# PWM_Sensor.net
KiCad netlist of a schematic drawn in Altium Designer
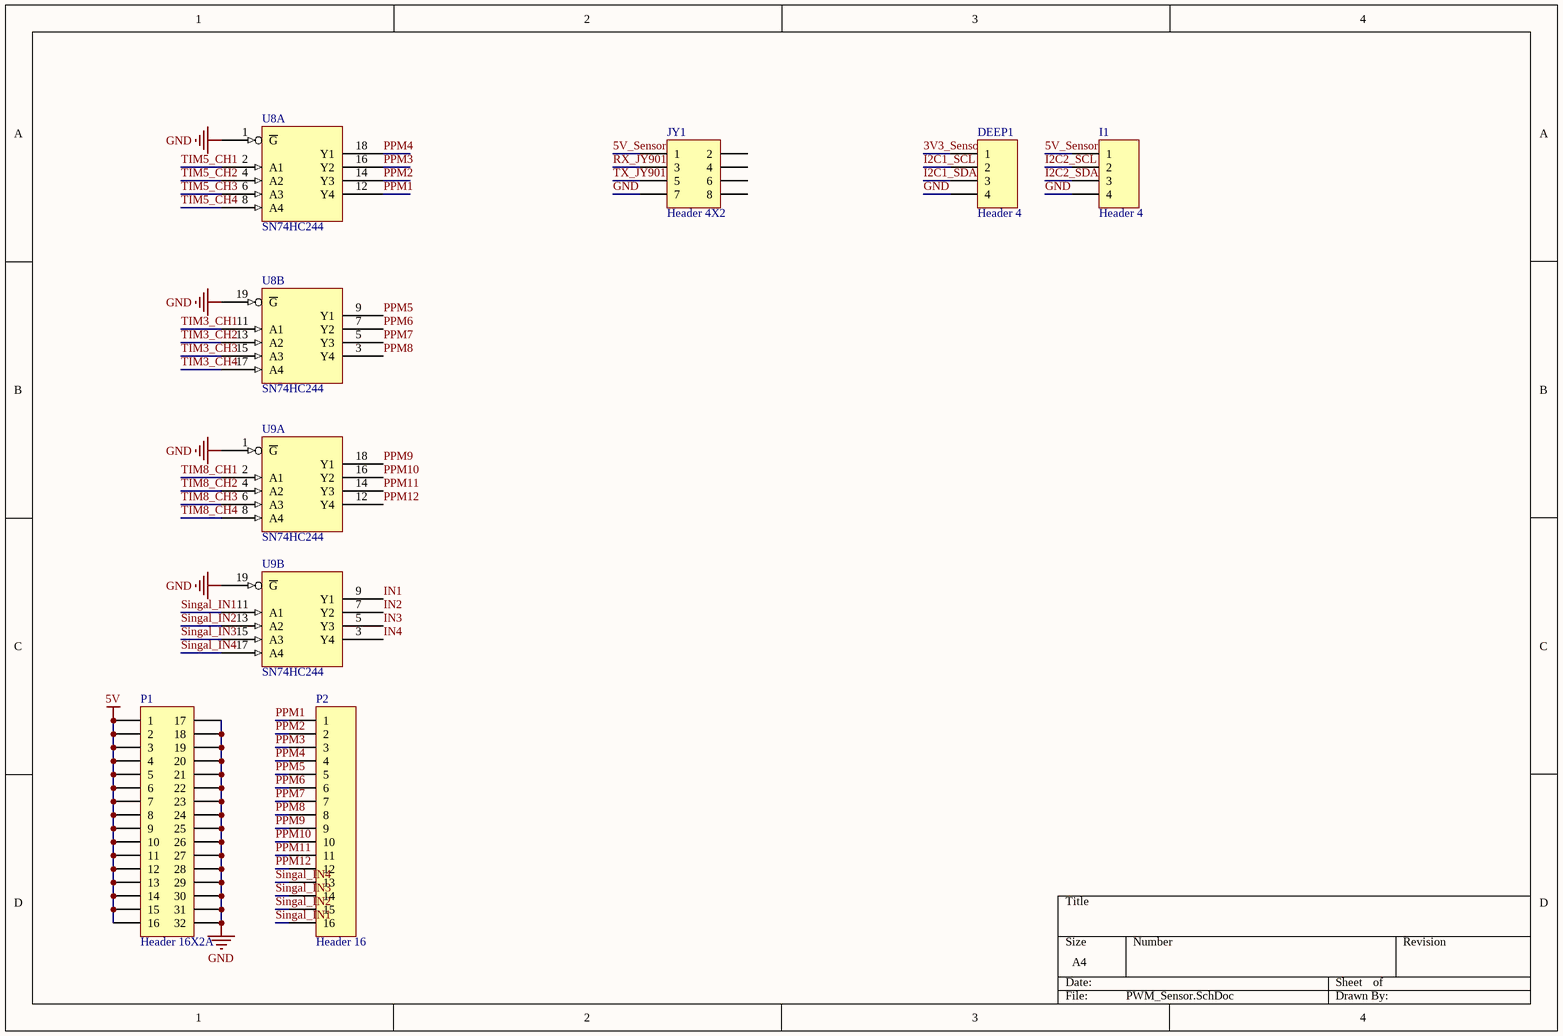
[diagram p0: PWM_Sensor.SchDoc]

(export (version "E")
  (design (tool "Eeschema 10.0.6"))
  (components
    (comp (ref "DEEP1")
      (value "Header 4")
      (footprint "XH2.54_4P")
      (description "Header, 4-Pin")
      (fields (field (name "PUBLISHER") "Altium Limited"))
      (libsource (lib "Miscellaneous Connectors") (part "Header 4"))
    )
    (comp (ref "I1")
      (value "Header 4")
      (footprint "XH2.54_4P")
      (description "Header, 4-Pin")
      (fields (field (name "PUBLISHER") "Altium Limited"))
      (libsource (lib "Miscellaneous Connectors") (part "Header 4"))
    )
    (comp (ref "JY1")
      (value "Header 4X2")
      (footprint "JY901_2")
      (description "Header, 4-Pin, Dual row")
      (fields (field (name "PUBLISHER") "Altium Limited"))
      (libsource (lib "Miscellaneous Connectors") (part "Header 4X2"))
    )
    (comp (ref "P1")
      (value "Header 16X2A")
      (footprint "HDR2X16_CEN")
      (description "Header, 16-Pin, Dual row")
      (fields (field (name "PUBLISHER") "Altium Limited"))
      (libsource (lib "Miscellaneous Connectors") (part "Header 16X2A"))
    )
    (comp (ref "P2")
      (value "Header 16")
      (footprint "HDR1X16")
      (description "Header, 16-Pin")
      (fields (field (name "PUBLISHER") "Altium Limited"))
      (libsource (lib "Miscellaneous Connectors") (part "Header 16"))
    )
    (comp (ref "U8")
      (value "SN74HC244")
      (footprint "SOIC-20_300mil")
      (description "OCTAL BUF AND LIN DRV 3SO")
      (libsource (lib "CMOS&TTL74") (part "SN74HC244"))
    )
    (comp (ref "U9")
      (value "SN74HC244")
      (footprint "SOIC-20_300mil")
      (description "OCTAL BUF AND LIN DRV 3SO")
      (libsource (lib "CMOS&TTL74") (part "SN74HC244"))
    )
  )
  (nets
    (net (code "1") (name "/3V3_Sensor") (class "Default")
      (node (ref "DEEP1") (pin "1") (pinfunction "1_1") (pintype "passive"))
    )
    (net (code "2") (name "/5V_Sensor") (class "Default")
      (node (ref "I1") (pin "1") (pinfunction "1_1") (pintype "passive"))
      (node (ref "JY1") (pin "1") (pinfunction "1_1") (pintype "passive"))
    )
    (net (code "3") (name "/I2C1_SCL") (class "Default")
      (node (ref "DEEP1") (pin "2") (pinfunction "2_2") (pintype "passive"))
    )
    (net (code "4") (name "/I2C1_SDA") (class "Default")
      (node (ref "DEEP1") (pin "3") (pinfunction "3_3") (pintype "passive"))
    )
    (net (code "5") (name "/I2C2_SCL") (class "Default")
      (node (ref "I1") (pin "2") (pinfunction "2_2") (pintype "passive"))
    )
    (net (code "6") (name "/I2C2_SDA") (class "Default")
      (node (ref "I1") (pin "3") (pinfunction "3_3") (pintype "passive"))
    )
    (net (code "7") (name "/IN1") (class "Default")
      (node (ref "U9") (pin "9") (pinfunction "Y1_9") (pintype "tri_state"))
    )
    (net (code "8") (name "/IN2") (class "Default")
      (node (ref "U9") (pin "7") (pinfunction "Y2_7") (pintype "tri_state"))
    )
    (net (code "9") (name "/IN3") (class "Default")
      (node (ref "U9") (pin "5") (pinfunction "Y3_5") (pintype "tri_state"))
    )
    (net (code "10") (name "/IN4") (class "Default")
      (node (ref "U9") (pin "3") (pinfunction "Y4_3") (pintype "tri_state"))
    )
    (net (code "11") (name "/PPM1") (class "Default")
      (node (ref "P2") (pin "1") (pinfunction "1_1") (pintype "passive"))
      (node (ref "U8") (pin "12") (pinfunction "Y4_12") (pintype "tri_state"))
    )
    (net (code "12") (name "/PPM2") (class "Default")
      (node (ref "P2") (pin "2") (pinfunction "2_2") (pintype "passive"))
      (node (ref "U8") (pin "14") (pinfunction "Y3_14") (pintype "tri_state"))
    )
    (net (code "13") (name "/PPM3") (class "Default")
      (node (ref "P2") (pin "3") (pinfunction "3_3") (pintype "passive"))
      (node (ref "U8") (pin "16") (pinfunction "Y2_16") (pintype "tri_state"))
    )
    (net (code "14") (name "/PPM4") (class "Default")
      (node (ref "P2") (pin "4") (pinfunction "4_4") (pintype "passive"))
      (node (ref "U8") (pin "18") (pinfunction "Y1_18") (pintype "tri_state"))
    )
    (net (code "15") (name "/PPM5") (class "Default")
      (node (ref "P2") (pin "5") (pinfunction "5_5") (pintype "passive"))
      (node (ref "U8") (pin "9") (pinfunction "Y1_9") (pintype "tri_state"))
    )
    (net (code "16") (name "/PPM6") (class "Default")
      (node (ref "P2") (pin "6") (pinfunction "6_6") (pintype "passive"))
      (node (ref "U8") (pin "7") (pinfunction "Y2_7") (pintype "tri_state"))
    )
    (net (code "17") (name "/PPM7") (class "Default")
      (node (ref "P2") (pin "7") (pinfunction "7_7") (pintype "passive"))
      (node (ref "U8") (pin "5") (pinfunction "Y3_5") (pintype "tri_state"))
    )
    (net (code "18") (name "/PPM8") (class "Default")
      (node (ref "P2") (pin "8") (pinfunction "8_8") (pintype "passive"))
      (node (ref "U8") (pin "3") (pinfunction "Y4_3") (pintype "tri_state"))
    )
    (net (code "19") (name "/PPM9") (class "Default")
      (node (ref "P2") (pin "9") (pinfunction "9_9") (pintype "passive"))
      (node (ref "U9") (pin "18") (pinfunction "Y1_18") (pintype "tri_state"))
    )
    (net (code "20") (name "/PPM10") (class "Default")
      (node (ref "P2") (pin "10") (pinfunction "10_10") (pintype "passive"))
      (node (ref "U9") (pin "16") (pinfunction "Y2_16") (pintype "tri_state"))
    )
    (net (code "21") (name "/PPM11") (class "Default")
      (node (ref "P2") (pin "11") (pinfunction "11_11") (pintype "passive"))
      (node (ref "U9") (pin "14") (pinfunction "Y3_14") (pintype "tri_state"))
    )
    (net (code "22") (name "/PPM12") (class "Default")
      (node (ref "P2") (pin "12") (pinfunction "12_12") (pintype "passive"))
      (node (ref "U9") (pin "12") (pinfunction "Y4_12") (pintype "tri_state"))
    )
    (net (code "23") (name "/RX_JY901") (class "Default")
      (node (ref "JY1") (pin "3") (pinfunction "3_3") (pintype "passive"))
    )
    (net (code "24") (name "/Singal_IN1") (class "Default")
      (node (ref "P2") (pin "16") (pinfunction "16_16") (pintype "passive"))
      (node (ref "U9") (pin "11") (pinfunction "A1_11") (pintype "input"))
    )
    (net (code "25") (name "/Singal_IN2") (class "Default")
      (node (ref "P2") (pin "15") (pinfunction "15_15") (pintype "passive"))
      (node (ref "U9") (pin "13") (pinfunction "A2_13") (pintype "input"))
    )
    (net (code "26") (name "/Singal_IN3") (class "Default")
      (node (ref "P2") (pin "14") (pinfunction "14_14") (pintype "passive"))
      (node (ref "U9") (pin "15") (pinfunction "A3_15") (pintype "input"))
    )
    (net (code "27") (name "/Singal_IN4") (class "Default")
      (node (ref "P2") (pin "13") (pinfunction "13_13") (pintype "passive"))
      (node (ref "U9") (pin "17") (pinfunction "A4_17") (pintype "input"))
    )
    (net (code "28") (name "/TIM3_CH1") (class "Default")
      (node (ref "U8") (pin "11") (pinfunction "A1_11") (pintype "input"))
    )
    (net (code "29") (name "/TIM3_CH2") (class "Default")
      (node (ref "U8") (pin "13") (pinfunction "A2_13") (pintype "input"))
    )
    (net (code "30") (name "/TIM3_CH3") (class "Default")
      (node (ref "U8") (pin "15") (pinfunction "A3_15") (pintype "input"))
    )
    (net (code "31") (name "/TIM3_CH4") (class "Default")
      (node (ref "U8") (pin "17") (pinfunction "A4_17") (pintype "input"))
    )
    (net (code "32") (name "/TIM5_CH1") (class "Default")
      (node (ref "U8") (pin "2") (pinfunction "A1_2") (pintype "input"))
    )
    (net (code "33") (name "/TIM5_CH2") (class "Default")
      (node (ref "U8") (pin "4") (pinfunction "A2_4") (pintype "input"))
    )
    (net (code "34") (name "/TIM5_CH3") (class "Default")
      (node (ref "U8") (pin "6") (pinfunction "A3_6") (pintype "input"))
    )
    (net (code "35") (name "/TIM5_CH4") (class "Default")
      (node (ref "U8") (pin "8") (pinfunction "A4_8") (pintype "input"))
    )
    (net (code "36") (name "/TIM8_CH1") (class "Default")
      (node (ref "U9") (pin "2") (pinfunction "A1_2") (pintype "input"))
    )
    (net (code "37") (name "/TIM8_CH2") (class "Default")
      (node (ref "U9") (pin "4") (pinfunction "A2_4") (pintype "input"))
    )
    (net (code "38") (name "/TIM8_CH3") (class "Default")
      (node (ref "U9") (pin "6") (pinfunction "A3_6") (pintype "input"))
    )
    (net (code "39") (name "/TIM8_CH4") (class "Default")
      (node (ref "U9") (pin "8") (pinfunction "A4_8") (pintype "input"))
    )
    (net (code "40") (name "/TX_JY901") (class "Default")
      (node (ref "JY1") (pin "5") (pinfunction "5_5") (pintype "passive"))
    )
    (net (code "41") (name "5V") (class "Default")
      (node (ref "P1") (pin "1") (pinfunction "1_1") (pintype "passive"))
      (node (ref "P1") (pin "10") (pinfunction "10_10") (pintype "passive"))
      (node (ref "P1") (pin "11") (pinfunction "11_11") (pintype "passive"))
      (node (ref "P1") (pin "12") (pinfunction "12_12") (pintype "passive"))
      (node (ref "P1") (pin "13") (pinfunction "13_13") (pintype "passive"))
      (node (ref "P1") (pin "14") (pinfunction "14_14") (pintype "passive"))
      (node (ref "P1") (pin "15") (pinfunction "15_15") (pintype "passive"))
      (node (ref "P1") (pin "16") (pinfunction "16_16") (pintype "passive"))
      (node (ref "P1") (pin "2") (pinfunction "2_2") (pintype "passive"))
      (node (ref "P1") (pin "3") (pinfunction "3_3") (pintype "passive"))
      (node (ref "P1") (pin "4") (pinfunction "4_4") (pintype "passive"))
      (node (ref "P1") (pin "5") (pinfunction "5_5") (pintype "passive"))
      (node (ref "P1") (pin "6") (pinfunction "6_6") (pintype "passive"))
      (node (ref "P1") (pin "7") (pinfunction "7_7") (pintype "passive"))
      (node (ref "P1") (pin "8") (pinfunction "8_8") (pintype "passive"))
      (node (ref "P1") (pin "9") (pinfunction "9_9") (pintype "passive"))
    )
    (net (code "42") (name "GND") (class "Default")
      (node (ref "DEEP1") (pin "4") (pinfunction "4_4") (pintype "passive"))
      (node (ref "I1") (pin "4") (pinfunction "4_4") (pintype "passive"))
      (node (ref "JY1") (pin "7") (pinfunction "7_7") (pintype "passive"))
      (node (ref "P1") (pin "17") (pinfunction "17_17") (pintype "passive"))
      (node (ref "P1") (pin "18") (pinfunction "18_18") (pintype "passive"))
      (node (ref "P1") (pin "19") (pinfunction "19_19") (pintype "passive"))
      (node (ref "P1") (pin "20") (pinfunction "20_20") (pintype "passive"))
      (node (ref "P1") (pin "21") (pinfunction "21_21") (pintype "passive"))
      (node (ref "P1") (pin "22") (pinfunction "22_22") (pintype "passive"))
      (node (ref "P1") (pin "23") (pinfunction "23_23") (pintype "passive"))
      (node (ref "P1") (pin "24") (pinfunction "24_24") (pintype "passive"))
      (node (ref "P1") (pin "25") (pinfunction "25_25") (pintype "passive"))
      (node (ref "P1") (pin "26") (pinfunction "26_26") (pintype "passive"))
      (node (ref "P1") (pin "27") (pinfunction "27_27") (pintype "passive"))
      (node (ref "P1") (pin "28") (pinfunction "28_28") (pintype "passive"))
      (node (ref "P1") (pin "29") (pinfunction "29_29") (pintype "passive"))
      (node (ref "P1") (pin "30") (pinfunction "30_30") (pintype "passive"))
      (node (ref "P1") (pin "31") (pinfunction "31_31") (pintype "passive"))
      (node (ref "P1") (pin "32") (pinfunction "32_32") (pintype "passive"))
      (node (ref "U8") (pin "1") (pinfunction "~{G}_1") (pintype "input"))
      (node (ref "U8") (pin "10") (pinfunction "GND_10") (pintype "power_in"))
      (node (ref "U8") (pin "19") (pinfunction "~{G}_19") (pintype "input"))
      (node (ref "U9") (pin "1") (pinfunction "~{G}_1") (pintype "input"))
      (node (ref "U9") (pin "10") (pinfunction "GND_10") (pintype "power_in"))
      (node (ref "U9") (pin "19") (pinfunction "~{G}_19") (pintype "input"))
    )
    (net (code "43") (name "VCC") (class "Default")
      (node (ref "U8") (pin "20") (pinfunction "VCC_20") (pintype "power_in"))
      (node (ref "U9") (pin "20") (pinfunction "VCC_20") (pintype "power_in"))
    )
    (net (code "44") (name "unconnected-(JY1-Pad2)") (class "Default")
      (node (ref "JY1") (pin "2") (pinfunction "2_2") (pintype "passive"))
    )
    (net (code "45") (name "unconnected-(JY1-Pad4)") (class "Default")
      (node (ref "JY1") (pin "4") (pinfunction "4_4") (pintype "passive"))
    )
    (net (code "46") (name "unconnected-(JY1-Pad6)") (class "Default")
      (node (ref "JY1") (pin "6") (pinfunction "6_6") (pintype "passive"))
    )
    (net (code "47") (name "unconnected-(JY1-Pad8)") (class "Default")
      (node (ref "JY1") (pin "8") (pinfunction "8_8") (pintype "passive"))
    )
  )
)
